# main.net
KiCad netlist of a schematic drawn in Altium Designer
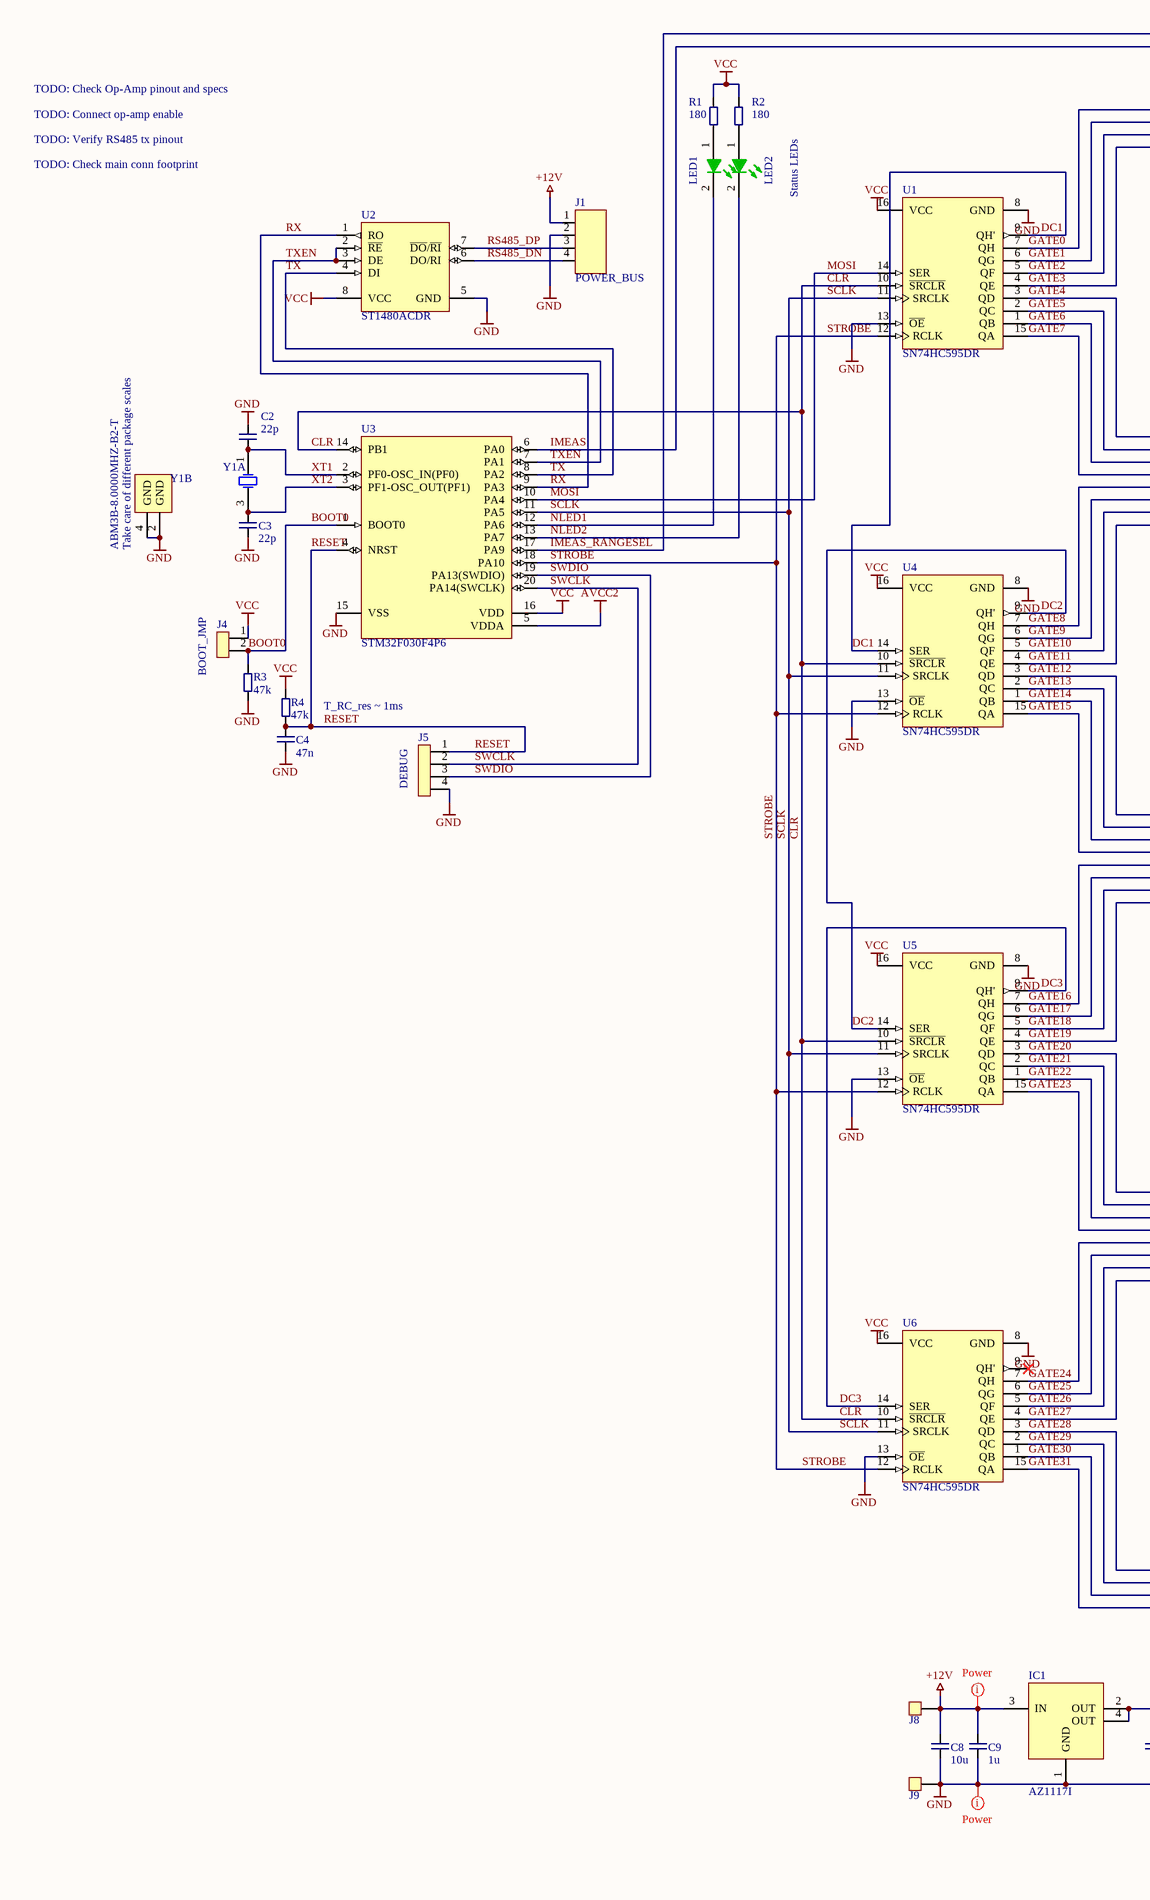
[diagram p0: main.SchDoc, left]
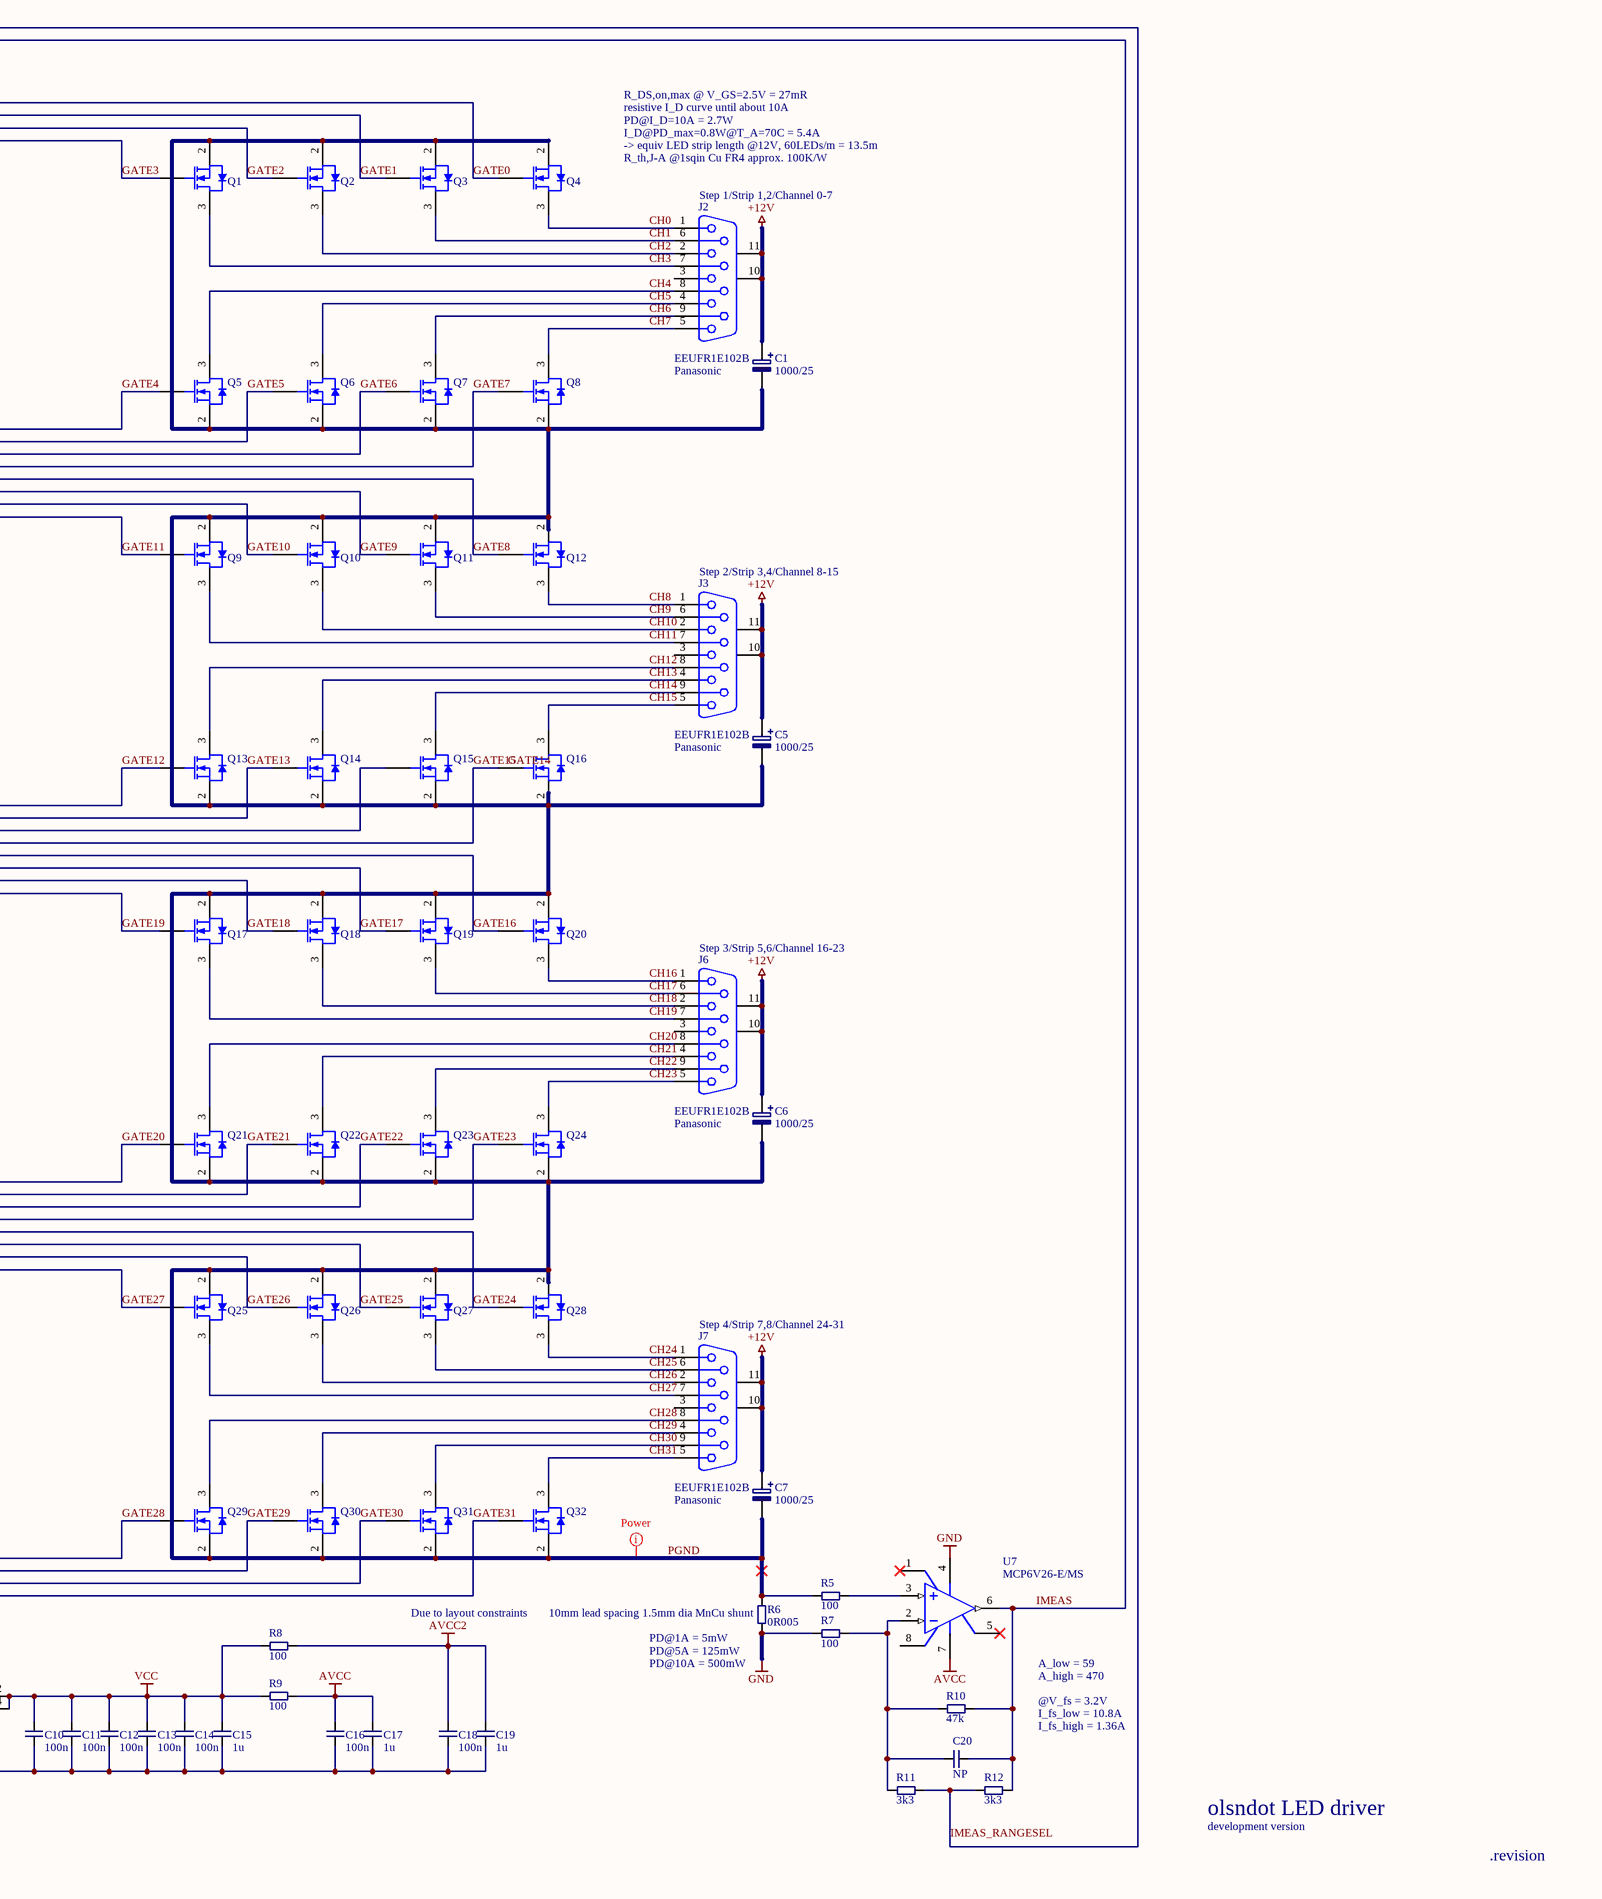
[diagram p1: main.SchDoc, right]

(export (version "E")
  (design (tool "Eeschema 10.0.6"))
  (components
    (comp (ref "C1")
      (value "1000/25")
      (footprint "ELKO_10mm_RM5")
      (fields (field (name "MFG PART NO") "EEUFR1E102B") (field (name "MFG") "Panasonic"))
      (libsource (lib "components") (part "ELKO"))
    )
    (comp (ref "C2")
      (value "22p")
      (footprint "J1-0603")
      (description "Capacitor")
      (libsource (lib "components") (part "C"))
    )
    (comp (ref "C3")
      (value "22p")
      (footprint "J1-0603")
      (description "Capacitor")
      (libsource (lib "components") (part "C"))
    )
    (comp (ref "C4")
      (value "47n")
      (footprint "J1-0603")
      (description "Capacitor")
      (libsource (lib "components") (part "C"))
    )
    (comp (ref "C5")
      (value "1000/25")
      (footprint "ELKO_10mm_RM5")
      (fields (field (name "MFG PART NO") "EEUFR1E102B") (field (name "MFG") "Panasonic"))
      (libsource (lib "components") (part "ELKO"))
    )
    (comp (ref "C6")
      (value "1000/25")
      (footprint "ELKO_10mm_RM5")
      (fields (field (name "MFG PART NO") "EEUFR1E102B") (field (name "MFG") "Panasonic"))
      (libsource (lib "components") (part "ELKO"))
    )
    (comp (ref "C7")
      (value "1000/25")
      (footprint "ELKO_10mm_RM5")
      (fields (field (name "MFG PART NO") "EEUFR1E102B") (field (name "MFG") "Panasonic"))
      (libsource (lib "components") (part "ELKO"))
    )
    (comp (ref "C8")
      (value "10u")
      (footprint "6-0805_M")
      (description "Capacitor")
      (libsource (lib "components") (part "C"))
    )
    (comp (ref "C9")
      (value "1u")
      (footprint "6-0805_M")
      (description "Capacitor")
      (libsource (lib "components") (part "C"))
    )
    (comp (ref "C10")
      (value "100n")
      (footprint "J1-0603")
      (description "Capacitor")
      (libsource (lib "components") (part "C"))
    )
    (comp (ref "C11")
      (value "100n")
      (footprint "J1-0603")
      (description "Capacitor")
      (libsource (lib "components") (part "C"))
    )
    (comp (ref "C12")
      (value "100n")
      (footprint "J1-0603")
      (description "Capacitor")
      (libsource (lib "components") (part "C"))
    )
    (comp (ref "C13")
      (value "100n")
      (footprint "J1-0603")
      (description "Capacitor")
      (libsource (lib "components") (part "C"))
    )
    (comp (ref "C14")
      (value "100n")
      (footprint "J1-0603")
      (description "Capacitor")
      (libsource (lib "components") (part "C"))
    )
    (comp (ref "C15")
      (value "1u")
      (footprint "6-0805_M")
      (description "Capacitor")
      (libsource (lib "components") (part "C"))
    )
    (comp (ref "C16")
      (value "100n")
      (footprint "J1-0603")
      (description "Capacitor")
      (libsource (lib "components") (part "C"))
    )
    (comp (ref "C17")
      (value "1u")
      (footprint "6-0805_M")
      (description "Capacitor")
      (libsource (lib "components") (part "C"))
    )
    (comp (ref "C18")
      (value "100n")
      (footprint "J1-0603")
      (description "Capacitor")
      (libsource (lib "components") (part "C"))
    )
    (comp (ref "C19")
      (value "1u")
      (footprint "J1-0603")
      (description "Capacitor")
      (libsource (lib "components") (part "C"))
    )
    (comp (ref "C20")
      (value "NP")
      (footprint "J1-0603")
      (description "Capacitor")
      (libsource (lib "components") (part "C"))
    )
    (comp (ref "IC1")
      (value "AZ1117I")
      (footprint "SOT223_M")
      (description "LDO, industrial temp range")
      (libsource (lib "components") (part "AZ1117I"))
    )
    (comp (ref "J1")
      (value "POWER_BUS")
      (footprint "TB_5.08_4P_FLANGE")
      (libsource (lib "components") (part "Phoenix_PT1,5/4-5,0H"))
    )
    (comp (ref "J2")
      (value "Step 1/Strip 1,2/Channel 0-7")
      (footprint "DSUB1.385-2H9")
      (description "Receptacle Assembly, 9 Position, Right Angle")
      (fields (field (name "PUBLISHER") "Altium Limited"))
      (libsource (lib "Miscellaneous Connectors") (part "D Connector 9"))
    )
    (comp (ref "J3")
      (value "Step 2/Strip 3,4/Channel 8-15")
      (footprint "DSUB1.385-2H9")
      (description "Receptacle Assembly, 9 Position, Right Angle")
      (fields (field (name "PUBLISHER") "Altium Limited"))
      (libsource (lib "Miscellaneous Connectors") (part "D Connector 9"))
    )
    (comp (ref "J4")
      (value "BOOT_JMP")
      (footprint "JUMPER_2P")
      (description "Jumper")
      (libsource (lib "components") (part "JUMPER"))
    )
    (comp (ref "J5")
      (value "DEBUG")
      (footprint "PINHD_4x1_100mil")
      (description "Pin Header 4x1 pin")
      (libsource (lib "components") (part "PH_4x1"))
    )
    (comp (ref "J6")
      (value "Step 3/Strip 5,6/Channel 16-23")
      (footprint "DSUB1.385-2H9")
      (description "Receptacle Assembly, 9 Position, Right Angle")
      (fields (field (name "PUBLISHER") "Altium Limited"))
      (libsource (lib "Miscellaneous Connectors") (part "D Connector 9"))
    )
    (comp (ref "J7")
      (value "Step 4/Strip 7,8/Channel 24-31")
      (footprint "DSUB1.385-2H9")
      (description "Receptacle Assembly, 9 Position, Right Angle")
      (fields (field (name "PUBLISHER") "Altium Limited"))
      (libsource (lib "Miscellaneous Connectors") (part "D Connector 9"))
    )
    (comp (ref "J8") (value "+12V") (libsource (lib "components") (part "TESTPOINT")))
    (comp (ref "J9") (value "GND") (libsource (lib "components") (part "TESTPOINT")))
    (comp (ref "LED1")
      (value "KP-1608MGC")
      (footprint "KING-0603LED_GREEN_V")
      (description "LED, SMT, 0603(1608), 1.1mm thickness, Green")
      (fields (field (name "MANUFACTURER") "Kingbright"))
      (libsource (lib "components") (part "CMP-0404-00001-1"))
    )
    (comp (ref "LED2")
      (value "KP-1608MGC")
      (footprint "KING-0603LED_GREEN_V")
      (description "LED, SMT, 0603(1608), 1.1mm thickness, Green")
      (fields (field (name "MANUFACTURER") "Kingbright"))
      (libsource (lib "components") (part "CMP-0404-00001-1"))
    )
    (comp (ref "Q1")
      (value "IRLML6244TRPbF")
      (footprint "ONSC-SOT-23-3-318-08_V")
      (description "Power MOSFET, 500 mA, 60 V, N-Channel, 3-Pin SOT-23, Pb-Free, Tape and Reel")
      (fields (field (name "MANUFACTURER") "On Semiconductor") (field (name "PARTNUMBER") "NVBF170LT1G"))
      (libsource (lib "Altium Content Vault") (part "ONSC-NMOS-G1S2D3-3"))
    )
    (comp (ref "Q2")
      (value "IRLML6244TRPbF")
      (footprint "ONSC-SOT-23-3-318-08_V")
      (description "Power MOSFET, 500 mA, 60 V, N-Channel, 3-Pin SOT-23, Pb-Free, Tape and Reel")
      (fields (field (name "MANUFACTURER") "On Semiconductor") (field (name "PARTNUMBER") "NVBF170LT1G"))
      (libsource (lib "Altium Content Vault") (part "ONSC-NMOS-G1S2D3-3"))
    )
    (comp (ref "Q3")
      (value "IRLML6244TRPbF")
      (footprint "ONSC-SOT-23-3-318-08_V")
      (description "Power MOSFET, 500 mA, 60 V, N-Channel, 3-Pin SOT-23, Pb-Free, Tape and Reel")
      (fields (field (name "MANUFACTURER") "On Semiconductor") (field (name "PARTNUMBER") "NVBF170LT1G"))
      (libsource (lib "Altium Content Vault") (part "ONSC-NMOS-G1S2D3-3"))
    )
    (comp (ref "Q4")
      (value "IRLML6244TRPbF")
      (footprint "ONSC-SOT-23-3-318-08_V")
      (description "Power MOSFET, 500 mA, 60 V, N-Channel, 3-Pin SOT-23, Pb-Free, Tape and Reel")
      (fields (field (name "MANUFACTURER") "On Semiconductor") (field (name "PARTNUMBER") "NVBF170LT1G"))
      (libsource (lib "Altium Content Vault") (part "ONSC-NMOS-G1S2D3-3"))
    )
    (comp (ref "Q5")
      (value "IRLML6244TRPbF")
      (footprint "ONSC-SOT-23-3-318-08_V")
      (description "Power MOSFET, 500 mA, 60 V, N-Channel, 3-Pin SOT-23, Pb-Free, Tape and Reel")
      (fields (field (name "MANUFACTURER") "On Semiconductor") (field (name "PARTNUMBER") "NVBF170LT1G"))
      (libsource (lib "Altium Content Vault") (part "ONSC-NMOS-G1S2D3-3"))
    )
    (comp (ref "Q6")
      (value "IRLML6244TRPbF")
      (footprint "ONSC-SOT-23-3-318-08_V")
      (description "Power MOSFET, 500 mA, 60 V, N-Channel, 3-Pin SOT-23, Pb-Free, Tape and Reel")
      (fields (field (name "MANUFACTURER") "On Semiconductor") (field (name "PARTNUMBER") "NVBF170LT1G"))
      (libsource (lib "Altium Content Vault") (part "ONSC-NMOS-G1S2D3-3"))
    )
    (comp (ref "Q7")
      (value "IRLML6244TRPbF")
      (footprint "ONSC-SOT-23-3-318-08_V")
      (description "Power MOSFET, 500 mA, 60 V, N-Channel, 3-Pin SOT-23, Pb-Free, Tape and Reel")
      (fields (field (name "MANUFACTURER") "On Semiconductor") (field (name "PARTNUMBER") "NVBF170LT1G"))
      (libsource (lib "Altium Content Vault") (part "ONSC-NMOS-G1S2D3-3"))
    )
    (comp (ref "Q8")
      (value "IRLML6244TRPbF")
      (footprint "ONSC-SOT-23-3-318-08_V")
      (description "Power MOSFET, 500 mA, 60 V, N-Channel, 3-Pin SOT-23, Pb-Free, Tape and Reel")
      (fields (field (name "MANUFACTURER") "On Semiconductor") (field (name "PARTNUMBER") "NVBF170LT1G"))
      (libsource (lib "Altium Content Vault") (part "ONSC-NMOS-G1S2D3-3"))
    )
    (comp (ref "Q9")
      (value "IRLML6244TRPbF")
      (footprint "ONSC-SOT-23-3-318-08_V")
      (description "Power MOSFET, 500 mA, 60 V, N-Channel, 3-Pin SOT-23, Pb-Free, Tape and Reel")
      (fields (field (name "MANUFACTURER") "On Semiconductor") (field (name "PARTNUMBER") "NVBF170LT1G"))
      (libsource (lib "Altium Content Vault") (part "ONSC-NMOS-G1S2D3-3"))
    )
    (comp (ref "Q10")
      (value "IRLML6244TRPbF")
      (footprint "ONSC-SOT-23-3-318-08_V")
      (description "Power MOSFET, 500 mA, 60 V, N-Channel, 3-Pin SOT-23, Pb-Free, Tape and Reel")
      (fields (field (name "MANUFACTURER") "On Semiconductor") (field (name "PARTNUMBER") "NVBF170LT1G"))
      (libsource (lib "Altium Content Vault") (part "ONSC-NMOS-G1S2D3-3"))
    )
    (comp (ref "Q11")
      (value "IRLML6244TRPbF")
      (footprint "ONSC-SOT-23-3-318-08_V")
      (description "Power MOSFET, 500 mA, 60 V, N-Channel, 3-Pin SOT-23, Pb-Free, Tape and Reel")
      (fields (field (name "MANUFACTURER") "On Semiconductor") (field (name "PARTNUMBER") "NVBF170LT1G"))
      (libsource (lib "Altium Content Vault") (part "ONSC-NMOS-G1S2D3-3"))
    )
    (comp (ref "Q12")
      (value "IRLML6244TRPbF")
      (footprint "ONSC-SOT-23-3-318-08_V")
      (description "Power MOSFET, 500 mA, 60 V, N-Channel, 3-Pin SOT-23, Pb-Free, Tape and Reel")
      (fields (field (name "MANUFACTURER") "On Semiconductor") (field (name "PARTNUMBER") "NVBF170LT1G"))
      (libsource (lib "Altium Content Vault") (part "ONSC-NMOS-G1S2D3-3"))
    )
    (comp (ref "Q13")
      (value "IRLML6244TRPbF")
      (footprint "ONSC-SOT-23-3-318-08_V")
      (description "Power MOSFET, 500 mA, 60 V, N-Channel, 3-Pin SOT-23, Pb-Free, Tape and Reel")
      (fields (field (name "MANUFACTURER") "On Semiconductor") (field (name "PARTNUMBER") "NVBF170LT1G"))
      (libsource (lib "Altium Content Vault") (part "ONSC-NMOS-G1S2D3-3"))
    )
    (comp (ref "Q14")
      (value "IRLML6244TRPbF")
      (footprint "ONSC-SOT-23-3-318-08_V")
      (description "Power MOSFET, 500 mA, 60 V, N-Channel, 3-Pin SOT-23, Pb-Free, Tape and Reel")
      (fields (field (name "MANUFACTURER") "On Semiconductor") (field (name "PARTNUMBER") "NVBF170LT1G"))
      (libsource (lib "Altium Content Vault") (part "ONSC-NMOS-G1S2D3-3"))
    )
    (comp (ref "Q15")
      (value "IRLML6244TRPbF")
      (footprint "ONSC-SOT-23-3-318-08_V")
      (description "Power MOSFET, 500 mA, 60 V, N-Channel, 3-Pin SOT-23, Pb-Free, Tape and Reel")
      (fields (field (name "MANUFACTURER") "On Semiconductor") (field (name "PARTNUMBER") "NVBF170LT1G"))
      (libsource (lib "Altium Content Vault") (part "ONSC-NMOS-G1S2D3-3"))
    )
    (comp (ref "Q16")
      (value "IRLML6244TRPbF")
      (footprint "ONSC-SOT-23-3-318-08_V")
      (description "Power MOSFET, 500 mA, 60 V, N-Channel, 3-Pin SOT-23, Pb-Free, Tape and Reel")
      (fields (field (name "MANUFACTURER") "On Semiconductor") (field (name "PARTNUMBER") "NVBF170LT1G"))
      (libsource (lib "Altium Content Vault") (part "ONSC-NMOS-G1S2D3-3"))
    )
    (comp (ref "Q17")
      (value "IRLML6244TRPbF")
      (footprint "ONSC-SOT-23-3-318-08_V")
      (description "Power MOSFET, 500 mA, 60 V, N-Channel, 3-Pin SOT-23, Pb-Free, Tape and Reel")
      (fields (field (name "MANUFACTURER") "On Semiconductor") (field (name "PARTNUMBER") "NVBF170LT1G"))
      (libsource (lib "Altium Content Vault") (part "ONSC-NMOS-G1S2D3-3"))
    )
    (comp (ref "Q18")
      (value "IRLML6244TRPbF")
      (footprint "ONSC-SOT-23-3-318-08_V")
      (description "Power MOSFET, 500 mA, 60 V, N-Channel, 3-Pin SOT-23, Pb-Free, Tape and Reel")
      (fields (field (name "MANUFACTURER") "On Semiconductor") (field (name "PARTNUMBER") "NVBF170LT1G"))
      (libsource (lib "Altium Content Vault") (part "ONSC-NMOS-G1S2D3-3"))
    )
    (comp (ref "Q19")
      (value "IRLML6244TRPbF")
      (footprint "ONSC-SOT-23-3-318-08_V")
      (description "Power MOSFET, 500 mA, 60 V, N-Channel, 3-Pin SOT-23, Pb-Free, Tape and Reel")
      (fields (field (name "MANUFACTURER") "On Semiconductor") (field (name "PARTNUMBER") "NVBF170LT1G"))
      (libsource (lib "Altium Content Vault") (part "ONSC-NMOS-G1S2D3-3"))
    )
    (comp (ref "Q20")
      (value "IRLML6244TRPbF")
      (footprint "ONSC-SOT-23-3-318-08_V")
      (description "Power MOSFET, 500 mA, 60 V, N-Channel, 3-Pin SOT-23, Pb-Free, Tape and Reel")
      (fields (field (name "MANUFACTURER") "On Semiconductor") (field (name "PARTNUMBER") "NVBF170LT1G"))
      (libsource (lib "Altium Content Vault") (part "ONSC-NMOS-G1S2D3-3"))
    )
    (comp (ref "Q21")
      (value "IRLML6244TRPbF")
      (footprint "ONSC-SOT-23-3-318-08_V")
      (description "Power MOSFET, 500 mA, 60 V, N-Channel, 3-Pin SOT-23, Pb-Free, Tape and Reel")
      (fields (field (name "MANUFACTURER") "On Semiconductor") (field (name "PARTNUMBER") "NVBF170LT1G"))
      (libsource (lib "Altium Content Vault") (part "ONSC-NMOS-G1S2D3-3"))
    )
    (comp (ref "Q22")
      (value "IRLML6244TRPbF")
      (footprint "ONSC-SOT-23-3-318-08_V")
      (description "Power MOSFET, 500 mA, 60 V, N-Channel, 3-Pin SOT-23, Pb-Free, Tape and Reel")
      (fields (field (name "MANUFACTURER") "On Semiconductor") (field (name "PARTNUMBER") "NVBF170LT1G"))
      (libsource (lib "Altium Content Vault") (part "ONSC-NMOS-G1S2D3-3"))
    )
    (comp (ref "Q23")
      (value "IRLML6244TRPbF")
      (footprint "ONSC-SOT-23-3-318-08_V")
      (description "Power MOSFET, 500 mA, 60 V, N-Channel, 3-Pin SOT-23, Pb-Free, Tape and Reel")
      (fields (field (name "MANUFACTURER") "On Semiconductor") (field (name "PARTNUMBER") "NVBF170LT1G"))
      (libsource (lib "Altium Content Vault") (part "ONSC-NMOS-G1S2D3-3"))
    )
    (comp (ref "Q24")
      (value "IRLML6244TRPbF")
      (footprint "ONSC-SOT-23-3-318-08_V")
      (description "Power MOSFET, 500 mA, 60 V, N-Channel, 3-Pin SOT-23, Pb-Free, Tape and Reel")
      (fields (field (name "MANUFACTURER") "On Semiconductor") (field (name "PARTNUMBER") "NVBF170LT1G"))
      (libsource (lib "Altium Content Vault") (part "ONSC-NMOS-G1S2D3-3"))
    )
    (comp (ref "Q25")
      (value "IRLML6244TRPbF")
      (footprint "ONSC-SOT-23-3-318-08_V")
      (description "Power MOSFET, 500 mA, 60 V, N-Channel, 3-Pin SOT-23, Pb-Free, Tape and Reel")
      (fields (field (name "MANUFACTURER") "On Semiconductor") (field (name "PARTNUMBER") "NVBF170LT1G"))
      (libsource (lib "Altium Content Vault") (part "ONSC-NMOS-G1S2D3-3"))
    )
    (comp (ref "Q26")
      (value "IRLML6244TRPbF")
      (footprint "ONSC-SOT-23-3-318-08_V")
      (description "Power MOSFET, 500 mA, 60 V, N-Channel, 3-Pin SOT-23, Pb-Free, Tape and Reel")
      (fields (field (name "MANUFACTURER") "On Semiconductor") (field (name "PARTNUMBER") "NVBF170LT1G"))
      (libsource (lib "Altium Content Vault") (part "ONSC-NMOS-G1S2D3-3"))
    )
    (comp (ref "Q27")
      (value "IRLML6244TRPbF")
      (footprint "ONSC-SOT-23-3-318-08_V")
      (description "Power MOSFET, 500 mA, 60 V, N-Channel, 3-Pin SOT-23, Pb-Free, Tape and Reel")
      (fields (field (name "MANUFACTURER") "On Semiconductor") (field (name "PARTNUMBER") "NVBF170LT1G"))
      (libsource (lib "Altium Content Vault") (part "ONSC-NMOS-G1S2D3-3"))
    )
    (comp (ref "Q28")
      (value "IRLML6244TRPbF")
      (footprint "ONSC-SOT-23-3-318-08_V")
      (description "Power MOSFET, 500 mA, 60 V, N-Channel, 3-Pin SOT-23, Pb-Free, Tape and Reel")
      (fields (field (name "MANUFACTURER") "On Semiconductor") (field (name "PARTNUMBER") "NVBF170LT1G"))
      (libsource (lib "Altium Content Vault") (part "ONSC-NMOS-G1S2D3-3"))
    )
    (comp (ref "Q29")
      (value "IRLML6244TRPbF")
      (footprint "ONSC-SOT-23-3-318-08_V")
      (description "Power MOSFET, 500 mA, 60 V, N-Channel, 3-Pin SOT-23, Pb-Free, Tape and Reel")
      (fields (field (name "MANUFACTURER") "On Semiconductor") (field (name "PARTNUMBER") "NVBF170LT1G"))
      (libsource (lib "Altium Content Vault") (part "ONSC-NMOS-G1S2D3-3"))
    )
    (comp (ref "Q30")
      (value "IRLML6244TRPbF")
      (footprint "ONSC-SOT-23-3-318-08_V")
      (description "Power MOSFET, 500 mA, 60 V, N-Channel, 3-Pin SOT-23, Pb-Free, Tape and Reel")
      (fields (field (name "MANUFACTURER") "On Semiconductor") (field (name "PARTNUMBER") "NVBF170LT1G"))
      (libsource (lib "Altium Content Vault") (part "ONSC-NMOS-G1S2D3-3"))
    )
    (comp (ref "Q31")
      (value "IRLML6244TRPbF")
      (footprint "ONSC-SOT-23-3-318-08_V")
      (description "Power MOSFET, 500 mA, 60 V, N-Channel, 3-Pin SOT-23, Pb-Free, Tape and Reel")
      (fields (field (name "MANUFACTURER") "On Semiconductor") (field (name "PARTNUMBER") "NVBF170LT1G"))
      (libsource (lib "Altium Content Vault") (part "ONSC-NMOS-G1S2D3-3"))
    )
    (comp (ref "Q32")
      (value "IRLML6244TRPbF")
      (footprint "ONSC-SOT-23-3-318-08_V")
      (description "Power MOSFET, 500 mA, 60 V, N-Channel, 3-Pin SOT-23, Pb-Free, Tape and Reel")
      (fields (field (name "MANUFACTURER") "On Semiconductor") (field (name "PARTNUMBER") "NVBF170LT1G"))
      (libsource (lib "Altium Content Vault") (part "ONSC-NMOS-G1S2D3-3"))
    )
    (comp (ref "R1")
      (value "180")
      (footprint "J1-0603")
      (description "Resistor")
      (libsource (lib "components") (part "R"))
    )
    (comp (ref "R2")
      (value "180")
      (footprint "J1-0603")
      (description "Resistor")
      (libsource (lib "components") (part "R"))
    )
    (comp (ref "R3")
      (value "47k")
      (footprint "J1-0603")
      (description "Resistor")
      (libsource (lib "components") (part "R"))
    )
    (comp (ref "R4")
      (value "47k")
      (footprint "J1-0603")
      (description "Resistor")
      (libsource (lib "components") (part "R"))
    )
    (comp (ref "R5")
      (value "100")
      (footprint "J1-0603")
      (description "Resistor")
      (libsource (lib "components") (part "R"))
    )
    (comp (ref "R6")
      (value "0R005")
      (footprint "10x1.5mm_Shunt")
      (description "Resistor")
      (fields (field (name "MECHANICAL") "10mm lead spacing 1.5mm dia MnCu shunt"))
      (libsource (lib "components") (part "R"))
    )
    (comp (ref "R7")
      (value "100")
      (footprint "J1-0603")
      (description "Resistor")
      (libsource (lib "components") (part "R"))
    )
    (comp (ref "R8")
      (value "100")
      (footprint "J1-0603")
      (description "Resistor")
      (libsource (lib "components") (part "R"))
    )
    (comp (ref "R9")
      (value "100")
      (footprint "J1-0603")
      (description "Resistor")
      (libsource (lib "components") (part "R"))
    )
    (comp (ref "R10")
      (value "47k")
      (footprint "J1-0603")
      (description "Resistor")
      (libsource (lib "components") (part "R"))
    )
    (comp (ref "R11")
      (value "3k3")
      (footprint "J1-0603")
      (description "Resistor")
      (libsource (lib "components") (part "R"))
    )
    (comp (ref "R12")
      (value "3k3")
      (footprint "J1-0603")
      (description "Resistor")
      (libsource (lib "components") (part "R"))
    )
    (comp (ref "U1")
      (value "SN74HC595DR")
      (footprint "D0016A_M")
      (description "8-Bit Shift Registers With 3-State Output Registers, D0016A, LARGE T&R")
      (fields
        (field (name "GENERIC PART NUMBER") "SN74HC595")
        (field (name "MANUFACTURER") "Texas Instruments")
      )
      (libsource (lib "Altium Content Vault") (part "CMP-0780-00037-3"))
    )
    (comp (ref "U2")
      (value "ST1480ACDR")
      (footprint "SO8_M")
      (description "Multipoint RS-485/RS-422 Transceiver, 8-pin Narrow SOIC")
      (fields (field (name "MANUFACTURER") "National Semiconductor"))
      (libsource (lib "components") (part "IN-LNTX-DS75176B"))
    )
    (comp (ref "U3")
      (value "STM32F030F4P6")
      (footprint "STM-TSSOP20_L")
      (libsource (lib "Altium Content Vault") (part "MC-ARM-STM32F030-IL20"))
    )
    (comp (ref "U4")
      (value "SN74HC595DR")
      (footprint "D0016A_M")
      (description "8-Bit Shift Registers With 3-State Output Registers, D0016A, LARGE T&R")
      (fields
        (field (name "GENERIC PART NUMBER") "SN74HC595")
        (field (name "MANUFACTURER") "Texas Instruments")
      )
      (libsource (lib "Altium Content Vault") (part "CMP-0780-00037-3"))
    )
    (comp (ref "U5")
      (value "SN74HC595DR")
      (footprint "D0016A_M")
      (description "8-Bit Shift Registers With 3-State Output Registers, D0016A, LARGE T&R")
      (fields
        (field (name "GENERIC PART NUMBER") "SN74HC595")
        (field (name "MANUFACTURER") "Texas Instruments")
      )
      (libsource (lib "Altium Content Vault") (part "CMP-0780-00037-3"))
    )
    (comp (ref "U6")
      (value "SN74HC595DR")
      (footprint "D0016A_M")
      (description "8-Bit Shift Registers With 3-State Output Registers, D0016A, LARGE T&R")
      (fields
        (field (name "GENERIC PART NUMBER") "SN74HC595")
        (field (name "MANUFACTURER") "Texas Instruments")
      )
      (libsource (lib "Altium Content Vault") (part "CMP-0780-00037-3"))
    )
    (comp (ref "U7")
      (value "MCP6V26-E/MS")
      (footprint "MSOP-MS8_N")
      (description "620 渭A, 2 MHz Auto-Zeroed Op Amp, 8-Pin MSOP, Extended Temperature")
      (libsource (lib "Altium Content Vault") (part "AMP-OPA-MCP6V26-IL8"))
    )
    (comp (ref "Y1")
      (value "ABM3B-8.0000MHZ-B2-T")
      (footprint "XTAL_MJ_5x3.2")
      (description "Crystal, SMD, 25.000000MHz Stab=50ppm 18.0pF")
      (fields
        (field (name "MANUFACTURER") "Abracon")
        (field (name "PARTNUMBER") "ABM3B-25.000MHZ-B2-T")
        (field (name "NOTE") "Take care of different package scales")
      )
      (libsource (lib "components") (part "ABRA-ABM3B-4"))
    )
  )
  (nets
    (net (code "1") (name "+12V") (class "Default")
      (node (ref "C1") (pin "1") (pinfunction "1_1") (pintype "passive"))
      (node (ref "C5") (pin "1") (pinfunction "1_1") (pintype "passive"))
      (node (ref "C6") (pin "1") (pinfunction "1_1") (pintype "passive"))
      (node (ref "C7") (pin "1") (pinfunction "1_1") (pintype "passive"))
      (node (ref "C8") (pin "1") (pinfunction "1_1") (pintype "passive"))
      (node (ref "C9") (pin "1") (pinfunction "1_1") (pintype "passive"))
      (node (ref "IC1") (pin "3") (pinfunction "IN_3") (pintype "passive"))
      (node (ref "J1") (pin "1") (pintype "passive"))
      (node (ref "J2") (pin "10") (pinfunction "MH1_10") (pintype "passive"))
      (node (ref "J2") (pin "11") (pinfunction "MH2_11") (pintype "passive"))
      (node (ref "J3") (pin "10") (pinfunction "MH1_10") (pintype "passive"))
      (node (ref "J3") (pin "11") (pinfunction "MH2_11") (pintype "passive"))
      (node (ref "J6") (pin "10") (pinfunction "MH1_10") (pintype "passive"))
      (node (ref "J6") (pin "11") (pinfunction "MH2_11") (pintype "passive"))
      (node (ref "J7") (pin "10") (pinfunction "MH1_10") (pintype "passive"))
      (node (ref "J7") (pin "11") (pinfunction "MH2_11") (pintype "passive"))
      (node (ref "J8") (pin "1") (pinfunction "1_1") (pintype "passive"))
    )
    (net (code "2") (name "/BOOT0") (class "Default")
      (node (ref "J4") (pin "2") (pinfunction "2_2") (pintype "passive"))
      (node (ref "R3") (pin "2") (pinfunction "2_2") (pintype "passive"))
      (node (ref "U3") (pin "1") (pinfunction "BOOT0_1") (pintype "input"))
    )
    (net (code "3") (name "/CH0") (class "Default")
      (node (ref "J2") (pin "1") (pinfunction "1_1") (pintype "passive"))
      (node (ref "Q4") (pin "3") (pinfunction "D_3") (pintype "passive"))
    )
    (net (code "4") (name "/CH1") (class "Default")
      (node (ref "J2") (pin "6") (pinfunction "6_6") (pintype "passive"))
      (node (ref "Q3") (pin "3") (pinfunction "D_3") (pintype "passive"))
    )
    (net (code "5") (name "/CH2") (class "Default")
      (node (ref "J2") (pin "2") (pinfunction "2_2") (pintype "passive"))
      (node (ref "Q2") (pin "3") (pinfunction "D_3") (pintype "passive"))
    )
    (net (code "6") (name "/CH3") (class "Default")
      (node (ref "J2") (pin "7") (pinfunction "7_7") (pintype "passive"))
      (node (ref "Q1") (pin "3") (pinfunction "D_3") (pintype "passive"))
    )
    (net (code "7") (name "/CH4") (class "Default")
      (node (ref "J2") (pin "8") (pinfunction "8_8") (pintype "passive"))
      (node (ref "Q5") (pin "3") (pinfunction "D_3") (pintype "passive"))
    )
    (net (code "8") (name "/CH5") (class "Default")
      (node (ref "J2") (pin "4") (pinfunction "4_4") (pintype "passive"))
      (node (ref "Q6") (pin "3") (pinfunction "D_3") (pintype "passive"))
    )
    (net (code "9") (name "/CH6") (class "Default")
      (node (ref "J2") (pin "9") (pinfunction "9_9") (pintype "passive"))
      (node (ref "Q7") (pin "3") (pinfunction "D_3") (pintype "passive"))
    )
    (net (code "10") (name "/CH7") (class "Default")
      (node (ref "J2") (pin "5") (pinfunction "5_5") (pintype "passive"))
      (node (ref "Q8") (pin "3") (pinfunction "D_3") (pintype "passive"))
    )
    (net (code "11") (name "/CH8") (class "Default")
      (node (ref "J3") (pin "1") (pinfunction "1_1") (pintype "passive"))
      (node (ref "Q12") (pin "3") (pinfunction "D_3") (pintype "passive"))
    )
    (net (code "12") (name "/CH9") (class "Default")
      (node (ref "J3") (pin "6") (pinfunction "6_6") (pintype "passive"))
      (node (ref "Q11") (pin "3") (pinfunction "D_3") (pintype "passive"))
    )
    (net (code "13") (name "/CH10") (class "Default")
      (node (ref "J3") (pin "2") (pinfunction "2_2") (pintype "passive"))
      (node (ref "Q10") (pin "3") (pinfunction "D_3") (pintype "passive"))
    )
    (net (code "14") (name "/CH11") (class "Default")
      (node (ref "J3") (pin "7") (pinfunction "7_7") (pintype "passive"))
      (node (ref "Q9") (pin "3") (pinfunction "D_3") (pintype "passive"))
    )
    (net (code "15") (name "/CH12") (class "Default")
      (node (ref "J3") (pin "8") (pinfunction "8_8") (pintype "passive"))
      (node (ref "Q13") (pin "3") (pinfunction "D_3") (pintype "passive"))
    )
    (net (code "16") (name "/CH13") (class "Default")
      (node (ref "J3") (pin "4") (pinfunction "4_4") (pintype "passive"))
      (node (ref "Q14") (pin "3") (pinfunction "D_3") (pintype "passive"))
    )
    (net (code "17") (name "/CH14") (class "Default")
      (node (ref "J3") (pin "9") (pinfunction "9_9") (pintype "passive"))
      (node (ref "Q15") (pin "3") (pinfunction "D_3") (pintype "passive"))
    )
    (net (code "18") (name "/CH15") (class "Default")
      (node (ref "J3") (pin "5") (pinfunction "5_5") (pintype "passive"))
      (node (ref "Q16") (pin "3") (pinfunction "D_3") (pintype "passive"))
    )
    (net (code "19") (name "/CH16") (class "Default")
      (node (ref "J6") (pin "1") (pinfunction "1_1") (pintype "passive"))
      (node (ref "Q20") (pin "3") (pinfunction "D_3") (pintype "passive"))
    )
    (net (code "20") (name "/CH17") (class "Default")
      (node (ref "J6") (pin "6") (pinfunction "6_6") (pintype "passive"))
      (node (ref "Q19") (pin "3") (pinfunction "D_3") (pintype "passive"))
    )
    (net (code "21") (name "/CH18") (class "Default")
      (node (ref "J6") (pin "2") (pinfunction "2_2") (pintype "passive"))
      (node (ref "Q18") (pin "3") (pinfunction "D_3") (pintype "passive"))
    )
    (net (code "22") (name "/CH19") (class "Default")
      (node (ref "J6") (pin "7") (pinfunction "7_7") (pintype "passive"))
      (node (ref "Q17") (pin "3") (pinfunction "D_3") (pintype "passive"))
    )
    (net (code "23") (name "/CH20") (class "Default")
      (node (ref "J6") (pin "8") (pinfunction "8_8") (pintype "passive"))
      (node (ref "Q21") (pin "3") (pinfunction "D_3") (pintype "passive"))
    )
    (net (code "24") (name "/CH21") (class "Default")
      (node (ref "J6") (pin "4") (pinfunction "4_4") (pintype "passive"))
      (node (ref "Q22") (pin "3") (pinfunction "D_3") (pintype "passive"))
    )
    (net (code "25") (name "/CH22") (class "Default")
      (node (ref "J6") (pin "9") (pinfunction "9_9") (pintype "passive"))
      (node (ref "Q23") (pin "3") (pinfunction "D_3") (pintype "passive"))
    )
    (net (code "26") (name "/CH23") (class "Default")
      (node (ref "J6") (pin "5") (pinfunction "5_5") (pintype "passive"))
      (node (ref "Q24") (pin "3") (pinfunction "D_3") (pintype "passive"))
    )
    (net (code "27") (name "/CH24") (class "Default")
      (node (ref "J7") (pin "1") (pinfunction "1_1") (pintype "passive"))
      (node (ref "Q28") (pin "3") (pinfunction "D_3") (pintype "passive"))
    )
    (net (code "28") (name "/CH25") (class "Default")
      (node (ref "J7") (pin "6") (pinfunction "6_6") (pintype "passive"))
      (node (ref "Q27") (pin "3") (pinfunction "D_3") (pintype "passive"))
    )
    (net (code "29") (name "/CH26") (class "Default")
      (node (ref "J7") (pin "2") (pinfunction "2_2") (pintype "passive"))
      (node (ref "Q26") (pin "3") (pinfunction "D_3") (pintype "passive"))
    )
    (net (code "30") (name "/CH27") (class "Default")
      (node (ref "J7") (pin "7") (pinfunction "7_7") (pintype "passive"))
      (node (ref "Q25") (pin "3") (pinfunction "D_3") (pintype "passive"))
    )
    (net (code "31") (name "/CH28") (class "Default")
      (node (ref "J7") (pin "8") (pinfunction "8_8") (pintype "passive"))
      (node (ref "Q29") (pin "3") (pinfunction "D_3") (pintype "passive"))
    )
    (net (code "32") (name "/CH29") (class "Default")
      (node (ref "J7") (pin "4") (pinfunction "4_4") (pintype "passive"))
      (node (ref "Q30") (pin "3") (pinfunction "D_3") (pintype "passive"))
    )
    (net (code "33") (name "/CH30") (class "Default")
      (node (ref "J7") (pin "9") (pinfunction "9_9") (pintype "passive"))
      (node (ref "Q31") (pin "3") (pinfunction "D_3") (pintype "passive"))
    )
    (net (code "34") (name "/CH31") (class "Default")
      (node (ref "J7") (pin "5") (pinfunction "5_5") (pintype "passive"))
      (node (ref "Q32") (pin "3") (pinfunction "D_3") (pintype "passive"))
    )
    (net (code "35") (name "/CLR") (class "Default")
      (node (ref "U1") (pin "10") (pinfunction "~{SRCLR}_10") (pintype "input"))
      (node (ref "U3") (pin "14") (pinfunction "PB1_14") (pintype "bidirectional"))
      (node (ref "U4") (pin "10") (pinfunction "~{SRCLR}_10") (pintype "input"))
      (node (ref "U5") (pin "10") (pinfunction "~{SRCLR}_10") (pintype "input"))
      (node (ref "U6") (pin "10") (pinfunction "~{SRCLR}_10") (pintype "input"))
    )
    (net (code "36") (name "/DC1") (class "Default")
      (node (ref "U1") (pin "9") (pinfunction "QH'_9") (pintype "output"))
      (node (ref "U4") (pin "14") (pinfunction "SER_14") (pintype "input"))
    )
    (net (code "37") (name "/DC2") (class "Default")
      (node (ref "U4") (pin "9") (pinfunction "QH'_9") (pintype "output"))
      (node (ref "U5") (pin "14") (pinfunction "SER_14") (pintype "input"))
    )
    (net (code "38") (name "/DC3") (class "Default")
      (node (ref "U5") (pin "9") (pinfunction "QH'_9") (pintype "output"))
      (node (ref "U6") (pin "14") (pinfunction "SER_14") (pintype "input"))
    )
    (net (code "39") (name "/GATE0") (class "Default")
      (node (ref "Q4") (pin "1") (pinfunction "G_1") (pintype "passive"))
      (node (ref "U1") (pin "7") (pinfunction "QH_7") (pintype "tri_state"))
    )
    (net (code "40") (name "/GATE1") (class "Default")
      (node (ref "Q3") (pin "1") (pinfunction "G_1") (pintype "passive"))
      (node (ref "U1") (pin "6") (pinfunction "QG_6") (pintype "tri_state"))
    )
    (net (code "41") (name "/GATE2") (class "Default")
      (node (ref "Q2") (pin "1") (pinfunction "G_1") (pintype "passive"))
      (node (ref "U1") (pin "5") (pinfunction "QF_5") (pintype "tri_state"))
    )
    (net (code "42") (name "/GATE3") (class "Default")
      (node (ref "Q1") (pin "1") (pinfunction "G_1") (pintype "passive"))
      (node (ref "U1") (pin "4") (pinfunction "QE_4") (pintype "tri_state"))
    )
    (net (code "43") (name "/GATE4") (class "Default")
      (node (ref "Q5") (pin "1") (pinfunction "G_1") (pintype "passive"))
      (node (ref "U1") (pin "3") (pinfunction "QD_3") (pintype "tri_state"))
    )
    (net (code "44") (name "/GATE5") (class "Default")
      (node (ref "Q6") (pin "1") (pinfunction "G_1") (pintype "passive"))
      (node (ref "U1") (pin "2") (pinfunction "QC_2") (pintype "tri_state"))
    )
    (net (code "45") (name "/GATE6") (class "Default")
      (node (ref "Q7") (pin "1") (pinfunction "G_1") (pintype "passive"))
      (node (ref "U1") (pin "1") (pinfunction "QB_1") (pintype "tri_state"))
    )
    (net (code "46") (name "/GATE7") (class "Default")
      (node (ref "Q8") (pin "1") (pinfunction "G_1") (pintype "passive"))
      (node (ref "U1") (pin "15") (pinfunction "QA_15") (pintype "tri_state"))
    )
    (net (code "47") (name "/GATE8") (class "Default")
      (node (ref "Q12") (pin "1") (pinfunction "G_1") (pintype "passive"))
      (node (ref "U4") (pin "7") (pinfunction "QH_7") (pintype "tri_state"))
    )
    (net (code "48") (name "/GATE9") (class "Default")
      (node (ref "Q11") (pin "1") (pinfunction "G_1") (pintype "passive"))
      (node (ref "U4") (pin "6") (pinfunction "QG_6") (pintype "tri_state"))
    )
    (net (code "49") (name "/GATE10") (class "Default")
      (node (ref "Q10") (pin "1") (pinfunction "G_1") (pintype "passive"))
      (node (ref "U4") (pin "5") (pinfunction "QF_5") (pintype "tri_state"))
    )
    (net (code "50") (name "/GATE11") (class "Default")
      (node (ref "Q9") (pin "1") (pinfunction "G_1") (pintype "passive"))
      (node (ref "U4") (pin "4") (pinfunction "QE_4") (pintype "tri_state"))
    )
    (net (code "51") (name "/GATE12") (class "Default")
      (node (ref "Q13") (pin "1") (pinfunction "G_1") (pintype "passive"))
      (node (ref "U4") (pin "3") (pinfunction "QD_3") (pintype "tri_state"))
    )
    (net (code "52") (name "/GATE13") (class "Default")
      (node (ref "Q14") (pin "1") (pinfunction "G_1") (pintype "passive"))
      (node (ref "U4") (pin "2") (pinfunction "QC_2") (pintype "tri_state"))
    )
    (net (code "53") (name "/GATE14") (class "Default")
      (node (ref "Q15") (pin "1") (pinfunction "G_1") (pintype "passive"))
      (node (ref "U4") (pin "1") (pinfunction "QB_1") (pintype "tri_state"))
    )
    (net (code "54") (name "/GATE15") (class "Default")
      (node (ref "Q16") (pin "1") (pinfunction "G_1") (pintype "passive"))
      (node (ref "U4") (pin "15") (pinfunction "QA_15") (pintype "tri_state"))
    )
    (net (code "55") (name "/GATE16") (class "Default")
      (node (ref "Q20") (pin "1") (pinfunction "G_1") (pintype "passive"))
      (node (ref "U5") (pin "7") (pinfunction "QH_7") (pintype "tri_state"))
    )
    (net (code "56") (name "/GATE17") (class "Default")
      (node (ref "Q19") (pin "1") (pinfunction "G_1") (pintype "passive"))
      (node (ref "U5") (pin "6") (pinfunction "QG_6") (pintype "tri_state"))
    )
    (net (code "57") (name "/GATE18") (class "Default")
      (node (ref "Q18") (pin "1") (pinfunction "G_1") (pintype "passive"))
      (node (ref "U5") (pin "5") (pinfunction "QF_5") (pintype "tri_state"))
    )
    (net (code "58") (name "/GATE19") (class "Default")
      (node (ref "Q17") (pin "1") (pinfunction "G_1") (pintype "passive"))
      (node (ref "U5") (pin "4") (pinfunction "QE_4") (pintype "tri_state"))
    )
    (net (code "59") (name "/GATE20") (class "Default")
      (node (ref "Q21") (pin "1") (pinfunction "G_1") (pintype "passive"))
      (node (ref "U5") (pin "3") (pinfunction "QD_3") (pintype "tri_state"))
    )
    (net (code "60") (name "/GATE21") (class "Default")
      (node (ref "Q22") (pin "1") (pinfunction "G_1") (pintype "passive"))
      (node (ref "U5") (pin "2") (pinfunction "QC_2") (pintype "tri_state"))
    )
    (net (code "61") (name "/GATE22") (class "Default")
      (node (ref "Q23") (pin "1") (pinfunction "G_1") (pintype "passive"))
      (node (ref "U5") (pin "1") (pinfunction "QB_1") (pintype "tri_state"))
    )
    (net (code "62") (name "/GATE23") (class "Default")
      (node (ref "Q24") (pin "1") (pinfunction "G_1") (pintype "passive"))
      (node (ref "U5") (pin "15") (pinfunction "QA_15") (pintype "tri_state"))
    )
    (net (code "63") (name "/GATE24") (class "Default")
      (node (ref "Q28") (pin "1") (pinfunction "G_1") (pintype "passive"))
      (node (ref "U6") (pin "7") (pinfunction "QH_7") (pintype "tri_state"))
    )
    (net (code "64") (name "/GATE25") (class "Default")
      (node (ref "Q27") (pin "1") (pinfunction "G_1") (pintype "passive"))
      (node (ref "U6") (pin "6") (pinfunction "QG_6") (pintype "tri_state"))
    )
    (net (code "65") (name "/GATE26") (class "Default")
      (node (ref "Q26") (pin "1") (pinfunction "G_1") (pintype "passive"))
      (node (ref "U6") (pin "5") (pinfunction "QF_5") (pintype "tri_state"))
    )
    (net (code "66") (name "/GATE27") (class "Default")
      (node (ref "Q25") (pin "1") (pinfunction "G_1") (pintype "passive"))
      (node (ref "U6") (pin "4") (pinfunction "QE_4") (pintype "tri_state"))
    )
    (net (code "67") (name "/GATE28") (class "Default")
      (node (ref "Q29") (pin "1") (pinfunction "G_1") (pintype "passive"))
      (node (ref "U6") (pin "3") (pinfunction "QD_3") (pintype "tri_state"))
    )
    (net (code "68") (name "/GATE29") (class "Default")
      (node (ref "Q30") (pin "1") (pinfunction "G_1") (pintype "passive"))
      (node (ref "U6") (pin "2") (pinfunction "QC_2") (pintype "tri_state"))
    )
    (net (code "69") (name "/GATE30") (class "Default")
      (node (ref "Q31") (pin "1") (pinfunction "G_1") (pintype "passive"))
      (node (ref "U6") (pin "1") (pinfunction "QB_1") (pintype "tri_state"))
    )
    (net (code "70") (name "/GATE31") (class "Default")
      (node (ref "Q32") (pin "1") (pinfunction "G_1") (pintype "passive"))
      (node (ref "U6") (pin "15") (pinfunction "QA_15") (pintype "tri_state"))
    )
    (net (code "71") (name "/IMEAS") (class "Default")
      (node (ref "C20") (pin "2") (pinfunction "2_2") (pintype "passive"))
      (node (ref "R10") (pin "2") (pinfunction "2_2") (pintype "passive"))
      (node (ref "R12") (pin "2") (pinfunction "2_2") (pintype "passive"))
      (node (ref "U3") (pin "6") (pinfunction "PA0_6") (pintype "bidirectional"))
      (node (ref "U7") (pin "6") (pinfunction "VOUT_6") (pintype "output"))
    )
    (net (code "72") (name "/IMEAS_RANGESEL") (class "Default")
      (node (ref "R11") (pin "2") (pinfunction "2_2") (pintype "passive"))
      (node (ref "R12") (pin "1") (pinfunction "1_1") (pintype "passive"))
      (node (ref "U3") (pin "17") (pinfunction "PA9_17") (pintype "bidirectional"))
    )
    (net (code "73") (name "/MOSI") (class "Default")
      (node (ref "U1") (pin "14") (pinfunction "SER_14") (pintype "input"))
      (node (ref "U3") (pin "10") (pinfunction "PA4_10") (pintype "bidirectional"))
    )
    (net (code "74") (name "/NLED1") (class "Default")
      (node (ref "LED1") (pin "2") (pinfunction "K_2") (pintype "passive"))
      (node (ref "U3") (pin "12") (pinfunction "PA6_12") (pintype "bidirectional"))
    )
    (net (code "75") (name "/NLED2") (class "Default")
      (node (ref "LED2") (pin "2") (pinfunction "K_2") (pintype "passive"))
      (node (ref "U3") (pin "13") (pinfunction "PA7_13") (pintype "bidirectional"))
    )
    (net (code "76") (name "/PGND") (class "Default")
      (node (ref "C1") (pin "2") (pinfunction "2_2") (pintype "passive"))
      (node (ref "C5") (pin "2") (pinfunction "2_2") (pintype "passive"))
      (node (ref "C6") (pin "2") (pinfunction "2_2") (pintype "passive"))
      (node (ref "C7") (pin "2") (pinfunction "2_2") (pintype "passive"))
      (node (ref "Q1") (pin "2") (pinfunction "S_2") (pintype "passive"))
      (node (ref "Q10") (pin "2") (pinfunction "S_2") (pintype "passive"))
      (node (ref "Q11") (pin "2") (pinfunction "S_2") (pintype "passive"))
      (node (ref "Q12") (pin "2") (pinfunction "S_2") (pintype "passive"))
      (node (ref "Q13") (pin "2") (pinfunction "S_2") (pintype "passive"))
      (node (ref "Q14") (pin "2") (pinfunction "S_2") (pintype "passive"))
      (node (ref "Q15") (pin "2") (pinfunction "S_2") (pintype "passive"))
      (node (ref "Q16") (pin "2") (pinfunction "S_2") (pintype "passive"))
      (node (ref "Q17") (pin "2") (pinfunction "S_2") (pintype "passive"))
      (node (ref "Q18") (pin "2") (pinfunction "S_2") (pintype "passive"))
      (node (ref "Q19") (pin "2") (pinfunction "S_2") (pintype "passive"))
      (node (ref "Q2") (pin "2") (pinfunction "S_2") (pintype "passive"))
      (node (ref "Q20") (pin "2") (pinfunction "S_2") (pintype "passive"))
      (node (ref "Q21") (pin "2") (pinfunction "S_2") (pintype "passive"))
      (node (ref "Q22") (pin "2") (pinfunction "S_2") (pintype "passive"))
      (node (ref "Q23") (pin "2") (pinfunction "S_2") (pintype "passive"))
      (node (ref "Q24") (pin "2") (pinfunction "S_2") (pintype "passive"))
      (node (ref "Q25") (pin "2") (pinfunction "S_2") (pintype "passive"))
      (node (ref "Q26") (pin "2") (pinfunction "S_2") (pintype "passive"))
      (node (ref "Q27") (pin "2") (pinfunction "S_2") (pintype "passive"))
      (node (ref "Q28") (pin "2") (pinfunction "S_2") (pintype "passive"))
      (node (ref "Q29") (pin "2") (pinfunction "S_2") (pintype "passive"))
      (node (ref "Q3") (pin "2") (pinfunction "S_2") (pintype "passive"))
      (node (ref "Q30") (pin "2") (pinfunction "S_2") (pintype "passive"))
      (node (ref "Q31") (pin "2") (pinfunction "S_2") (pintype "passive"))
      (node (ref "Q32") (pin "2") (pinfunction "S_2") (pintype "passive"))
      (node (ref "Q4") (pin "2") (pinfunction "S_2") (pintype "passive"))
      (node (ref "Q5") (pin "2") (pinfunction "S_2") (pintype "passive"))
      (node (ref "Q6") (pin "2") (pinfunction "S_2") (pintype "passive"))
      (node (ref "Q7") (pin "2") (pinfunction "S_2") (pintype "passive"))
      (node (ref "Q8") (pin "2") (pinfunction "S_2") (pintype "passive"))
      (node (ref "Q9") (pin "2") (pinfunction "S_2") (pintype "passive"))
      (node (ref "R5") (pin "1") (pinfunction "1_1") (pintype "passive"))
      (node (ref "R6") (pin "1") (pinfunction "1_1") (pintype "passive"))
    )
    (net (code "77") (name "/RESET") (class "Default")
      (node (ref "C4") (pin "1") (pinfunction "1_1") (pintype "passive"))
      (node (ref "J5") (pin "1") (pinfunction "1_1") (pintype "passive"))
      (node (ref "R4") (pin "1") (pinfunction "1_1") (pintype "passive"))
      (node (ref "U3") (pin "4") (pinfunction "NRST_4") (pintype "bidirectional"))
    )
    (net (code "78") (name "/RS485_DN") (class "Default")
      (node (ref "J1") (pin "4") (pintype "passive"))
      (node (ref "U2") (pin "6") (pinfunction "DO/RI_6") (pintype "bidirectional"))
    )
    (net (code "79") (name "/RS485_DP") (class "Default")
      (node (ref "J1") (pin "3") (pintype "passive"))
      (node (ref "U2") (pin "7") (pinfunction "~{DO}/~{RI}_7") (pintype "bidirectional"))
    )
    (net (code "80") (name "/RX") (class "Default")
      (node (ref "U2") (pin "1") (pinfunction "RO_1") (pintype "output"))
      (node (ref "U3") (pin "9") (pinfunction "PA3_9") (pintype "bidirectional"))
    )
    (net (code "81") (name "/SCLK") (class "Default")
      (node (ref "U1") (pin "11") (pinfunction "SRCLK_11") (pintype "input"))
      (node (ref "U3") (pin "11") (pinfunction "PA5_11") (pintype "bidirectional"))
      (node (ref "U4") (pin "11") (pinfunction "SRCLK_11") (pintype "input"))
      (node (ref "U5") (pin "11") (pinfunction "SRCLK_11") (pintype "input"))
      (node (ref "U6") (pin "11") (pinfunction "SRCLK_11") (pintype "input"))
    )
    (net (code "82") (name "/STROBE") (class "Default")
      (node (ref "U1") (pin "12") (pinfunction "RCLK_12") (pintype "input"))
      (node (ref "U3") (pin "18") (pinfunction "PA10_18") (pintype "bidirectional"))
      (node (ref "U4") (pin "12") (pinfunction "RCLK_12") (pintype "input"))
      (node (ref "U5") (pin "12") (pinfunction "RCLK_12") (pintype "input"))
      (node (ref "U6") (pin "12") (pinfunction "RCLK_12") (pintype "input"))
    )
    (net (code "83") (name "/SWCLK") (class "Default")
      (node (ref "J5") (pin "2") (pinfunction "2_2") (pintype "passive"))
      (node (ref "U3") (pin "20") (pinfunction "PA14(SWCLK)_20") (pintype "bidirectional"))
    )
    (net (code "84") (name "/SWDIO") (class "Default")
      (node (ref "J5") (pin "3") (pinfunction "3_3") (pintype "passive"))
      (node (ref "U3") (pin "19") (pinfunction "PA13(SWDIO)_19") (pintype "bidirectional"))
    )
    (net (code "85") (name "/TX") (class "Default")
      (node (ref "U2") (pin "4") (pinfunction "DI_4") (pintype "input"))
      (node (ref "U3") (pin "8") (pinfunction "PA2_8") (pintype "bidirectional"))
    )
    (net (code "86") (name "/TXEN") (class "Default")
      (node (ref "U2") (pin "2") (pinfunction "~{RE}_2") (pintype "input"))
      (node (ref "U2") (pin "3") (pinfunction "DE_3") (pintype "input"))
      (node (ref "U3") (pin "7") (pinfunction "PA1_7") (pintype "bidirectional"))
    )
    (net (code "87") (name "/XT1") (class "Default")
      (node (ref "C2") (pin "2") (pinfunction "2_2") (pintype "passive"))
      (node (ref "U3") (pin "2") (pinfunction "PF0-OSC_IN(PF0)_2") (pintype "bidirectional"))
      (node (ref "Y1") (pin "1") (pinfunction "X1_1") (pintype "passive"))
    )
    (net (code "88") (name "/XT2") (class "Default")
      (node (ref "C3") (pin "1") (pinfunction "1_1") (pintype "passive"))
      (node (ref "U3") (pin "3") (pinfunction "PF1-OSC_OUT(PF1)_3") (pintype "bidirectional"))
      (node (ref "Y1") (pin "3") (pinfunction "X2_3") (pintype "passive"))
    )
    (net (code "89") (name "AVCC") (class "Default")
      (node (ref "C16") (pin "1") (pinfunction "1_1") (pintype "passive"))
      (node (ref "C17") (pin "1") (pinfunction "1_1") (pintype "passive"))
      (node (ref "R9") (pin "2") (pinfunction "2_2") (pintype "passive"))
      (node (ref "U7") (pin "7") (pinfunction "VDD_7") (pintype "power_in"))
    )
    (net (code "90") (name "AVCC2") (class "Default")
      (node (ref "C18") (pin "1") (pinfunction "1_1") (pintype "passive"))
      (node (ref "C19") (pin "1") (pinfunction "1_1") (pintype "passive"))
      (node (ref "R8") (pin "2") (pinfunction "2_2") (pintype "passive"))
      (node (ref "U3") (pin "5") (pinfunction "VDDA_5") (pintype "power_in"))
    )
    (net (code "91") (name "GND") (class "Default")
      (node (ref "C10") (pin "2") (pinfunction "2_2") (pintype "passive"))
      (node (ref "C11") (pin "2") (pinfunction "2_2") (pintype "passive"))
      (node (ref "C12") (pin "2") (pinfunction "2_2") (pintype "passive"))
      (node (ref "C13") (pin "2") (pinfunction "2_2") (pintype "passive"))
      (node (ref "C14") (pin "2") (pinfunction "2_2") (pintype "passive"))
      (node (ref "C15") (pin "2") (pinfunction "2_2") (pintype "passive"))
      (node (ref "C16") (pin "2") (pinfunction "2_2") (pintype "passive"))
      (node (ref "C17") (pin "2") (pinfunction "2_2") (pintype "passive"))
      (node (ref "C18") (pin "2") (pinfunction "2_2") (pintype "passive"))
      (node (ref "C19") (pin "2") (pinfunction "2_2") (pintype "passive"))
      (node (ref "C2") (pin "1") (pinfunction "1_1") (pintype "passive"))
      (node (ref "C3") (pin "2") (pinfunction "2_2") (pintype "passive"))
      (node (ref "C4") (pin "2") (pinfunction "2_2") (pintype "passive"))
      (node (ref "C8") (pin "2") (pinfunction "2_2") (pintype "passive"))
      (node (ref "C9") (pin "2") (pinfunction "2_2") (pintype "passive"))
      (node (ref "IC1") (pin "1") (pinfunction "GND_1") (pintype "passive"))
      (node (ref "J1") (pin "2") (pintype "passive"))
      (node (ref "J5") (pin "4") (pinfunction "4_4") (pintype "passive"))
      (node (ref "J9") (pin "1") (pinfunction "1_1") (pintype "passive"))
      (node (ref "R3") (pin "1") (pinfunction "1_1") (pintype "passive"))
      (node (ref "R6") (pin "2") (pinfunction "2_2") (pintype "passive"))
      (node (ref "R7") (pin "1") (pinfunction "1_1") (pintype "passive"))
      (node (ref "U1") (pin "13") (pinfunction "~{OE}_13") (pintype "input"))
      (node (ref "U1") (pin "8") (pinfunction "GND_8") (pintype "power_in"))
      (node (ref "U2") (pin "5") (pinfunction "GND_5") (pintype "power_in"))
      (node (ref "U3") (pin "15") (pinfunction "VSS_15") (pintype "power_in"))
      (node (ref "U4") (pin "13") (pinfunction "~{OE}_13") (pintype "input"))
      (node (ref "U4") (pin "8") (pinfunction "GND_8") (pintype "power_in"))
      (node (ref "U5") (pin "13") (pinfunction "~{OE}_13") (pintype "input"))
      (node (ref "U5") (pin "8") (pinfunction "GND_8") (pintype "power_in"))
      (node (ref "U6") (pin "13") (pinfunction "~{OE}_13") (pintype "input"))
      (node (ref "U6") (pin "8") (pinfunction "GND_8") (pintype "power_in"))
      (node (ref "U7") (pin "4") (pinfunction "VSS_4") (pintype "power_in"))
      (node (ref "Y1") (pin "2") (pinfunction "GND_2") (pintype "power_in"))
      (node (ref "Y1") (pin "4") (pinfunction "GND_4") (pintype "power_in"))
    )
    (net (code "92") (name "Net-(LED1-A)") (class "Default")
      (node (ref "LED1") (pin "1") (pinfunction "A_1") (pintype "passive"))
      (node (ref "R1") (pin "1") (pinfunction "1_1") (pintype "passive"))
    )
    (net (code "93") (name "Net-(LED2-A)") (class "Default")
      (node (ref "LED2") (pin "1") (pinfunction "A_1") (pintype "passive"))
      (node (ref "R2") (pin "1") (pinfunction "1_1") (pintype "passive"))
    )
    (net (code "94") (name "Net-(U7-VIN+)") (class "Default")
      (node (ref "R5") (pin "2") (pinfunction "2_2") (pintype "passive"))
      (node (ref "U7") (pin "3") (pinfunction "VIN+_3") (pintype "input"))
    )
    (net (code "95") (name "Net-(U7-VIN-)") (class "Default")
      (node (ref "C20") (pin "1") (pinfunction "1_1") (pintype "passive"))
      (node (ref "R10") (pin "1") (pinfunction "1_1") (pintype "passive"))
      (node (ref "R11") (pin "1") (pinfunction "1_1") (pintype "passive"))
      (node (ref "R7") (pin "2") (pinfunction "2_2") (pintype "passive"))
      (node (ref "U7") (pin "2") (pinfunction "VIN-_2") (pintype "input"))
    )
    (net (code "96") (name "VCC") (class "Default")
      (node (ref "C10") (pin "1") (pinfunction "1_1") (pintype "passive"))
      (node (ref "C11") (pin "1") (pinfunction "1_1") (pintype "passive"))
      (node (ref "C12") (pin "1") (pinfunction "1_1") (pintype "passive"))
      (node (ref "C13") (pin "1") (pinfunction "1_1") (pintype "passive"))
      (node (ref "C14") (pin "1") (pinfunction "1_1") (pintype "passive"))
      (node (ref "C15") (pin "1") (pinfunction "1_1") (pintype "passive"))
      (node (ref "IC1") (pin "2") (pinfunction "OUT_2") (pintype "passive"))
      (node (ref "IC1") (pin "4") (pinfunction "OUT_4") (pintype "passive"))
      (node (ref "J4") (pin "1") (pinfunction "1_1") (pintype "passive"))
      (node (ref "R1") (pin "2") (pinfunction "2_2") (pintype "passive"))
      (node (ref "R2") (pin "2") (pinfunction "2_2") (pintype "passive"))
      (node (ref "R4") (pin "2") (pinfunction "2_2") (pintype "passive"))
      (node (ref "R8") (pin "1") (pinfunction "1_1") (pintype "passive"))
      (node (ref "R9") (pin "1") (pinfunction "1_1") (pintype "passive"))
      (node (ref "U1") (pin "16") (pinfunction "VCC_16") (pintype "power_in"))
      (node (ref "U2") (pin "8") (pinfunction "VCC_8") (pintype "power_in"))
      (node (ref "U3") (pin "16") (pinfunction "VDD_16") (pintype "power_in"))
      (node (ref "U4") (pin "16") (pinfunction "VCC_16") (pintype "power_in"))
      (node (ref "U5") (pin "16") (pinfunction "VCC_16") (pintype "power_in"))
      (node (ref "U6") (pin "16") (pinfunction "VCC_16") (pintype "power_in"))
    )
    (net (code "97") (name "unconnected-(J2-Pad3)") (class "Default")
      (node (ref "J2") (pin "3") (pinfunction "3_3") (pintype "passive"))
    )
    (net (code "98") (name "unconnected-(J3-Pad3)") (class "Default")
      (node (ref "J3") (pin "3") (pinfunction "3_3") (pintype "passive"))
    )
    (net (code "99") (name "unconnected-(J6-Pad3)") (class "Default")
      (node (ref "J6") (pin "3") (pinfunction "3_3") (pintype "passive"))
    )
    (net (code "100") (name "unconnected-(J7-Pad3)") (class "Default")
      (node (ref "J7") (pin "3") (pinfunction "3_3") (pintype "passive"))
    )
    (net (code "101") (name "unconnected-(U6-QH'-Pad9)") (class "Default")
      (node (ref "U6") (pin "9") (pinfunction "QH'_9") (pintype "output+no_connect"))
    )
    (net (code "102") (name "unconnected-(U7-NC-Pad1)") (class "Default")
      (node (ref "U7") (pin "1") (pinfunction "NC_1") (pintype "passive+no_connect"))
    )
    (net (code "103") (name "unconnected-(U7-NC-Pad5)") (class "Default")
      (node (ref "U7") (pin "5") (pinfunction "NC_5") (pintype "passive+no_connect"))
    )
    (net (code "104") (name "unconnected-(U7-NC-Pad8)") (class "Default")
      (node (ref "U7") (pin "8") (pinfunction "NC_8") (pintype "passive"))
    )
  )
)
